# aux_opto_isolation.net
KiCad netlist of a schematic drawn in EAGLE
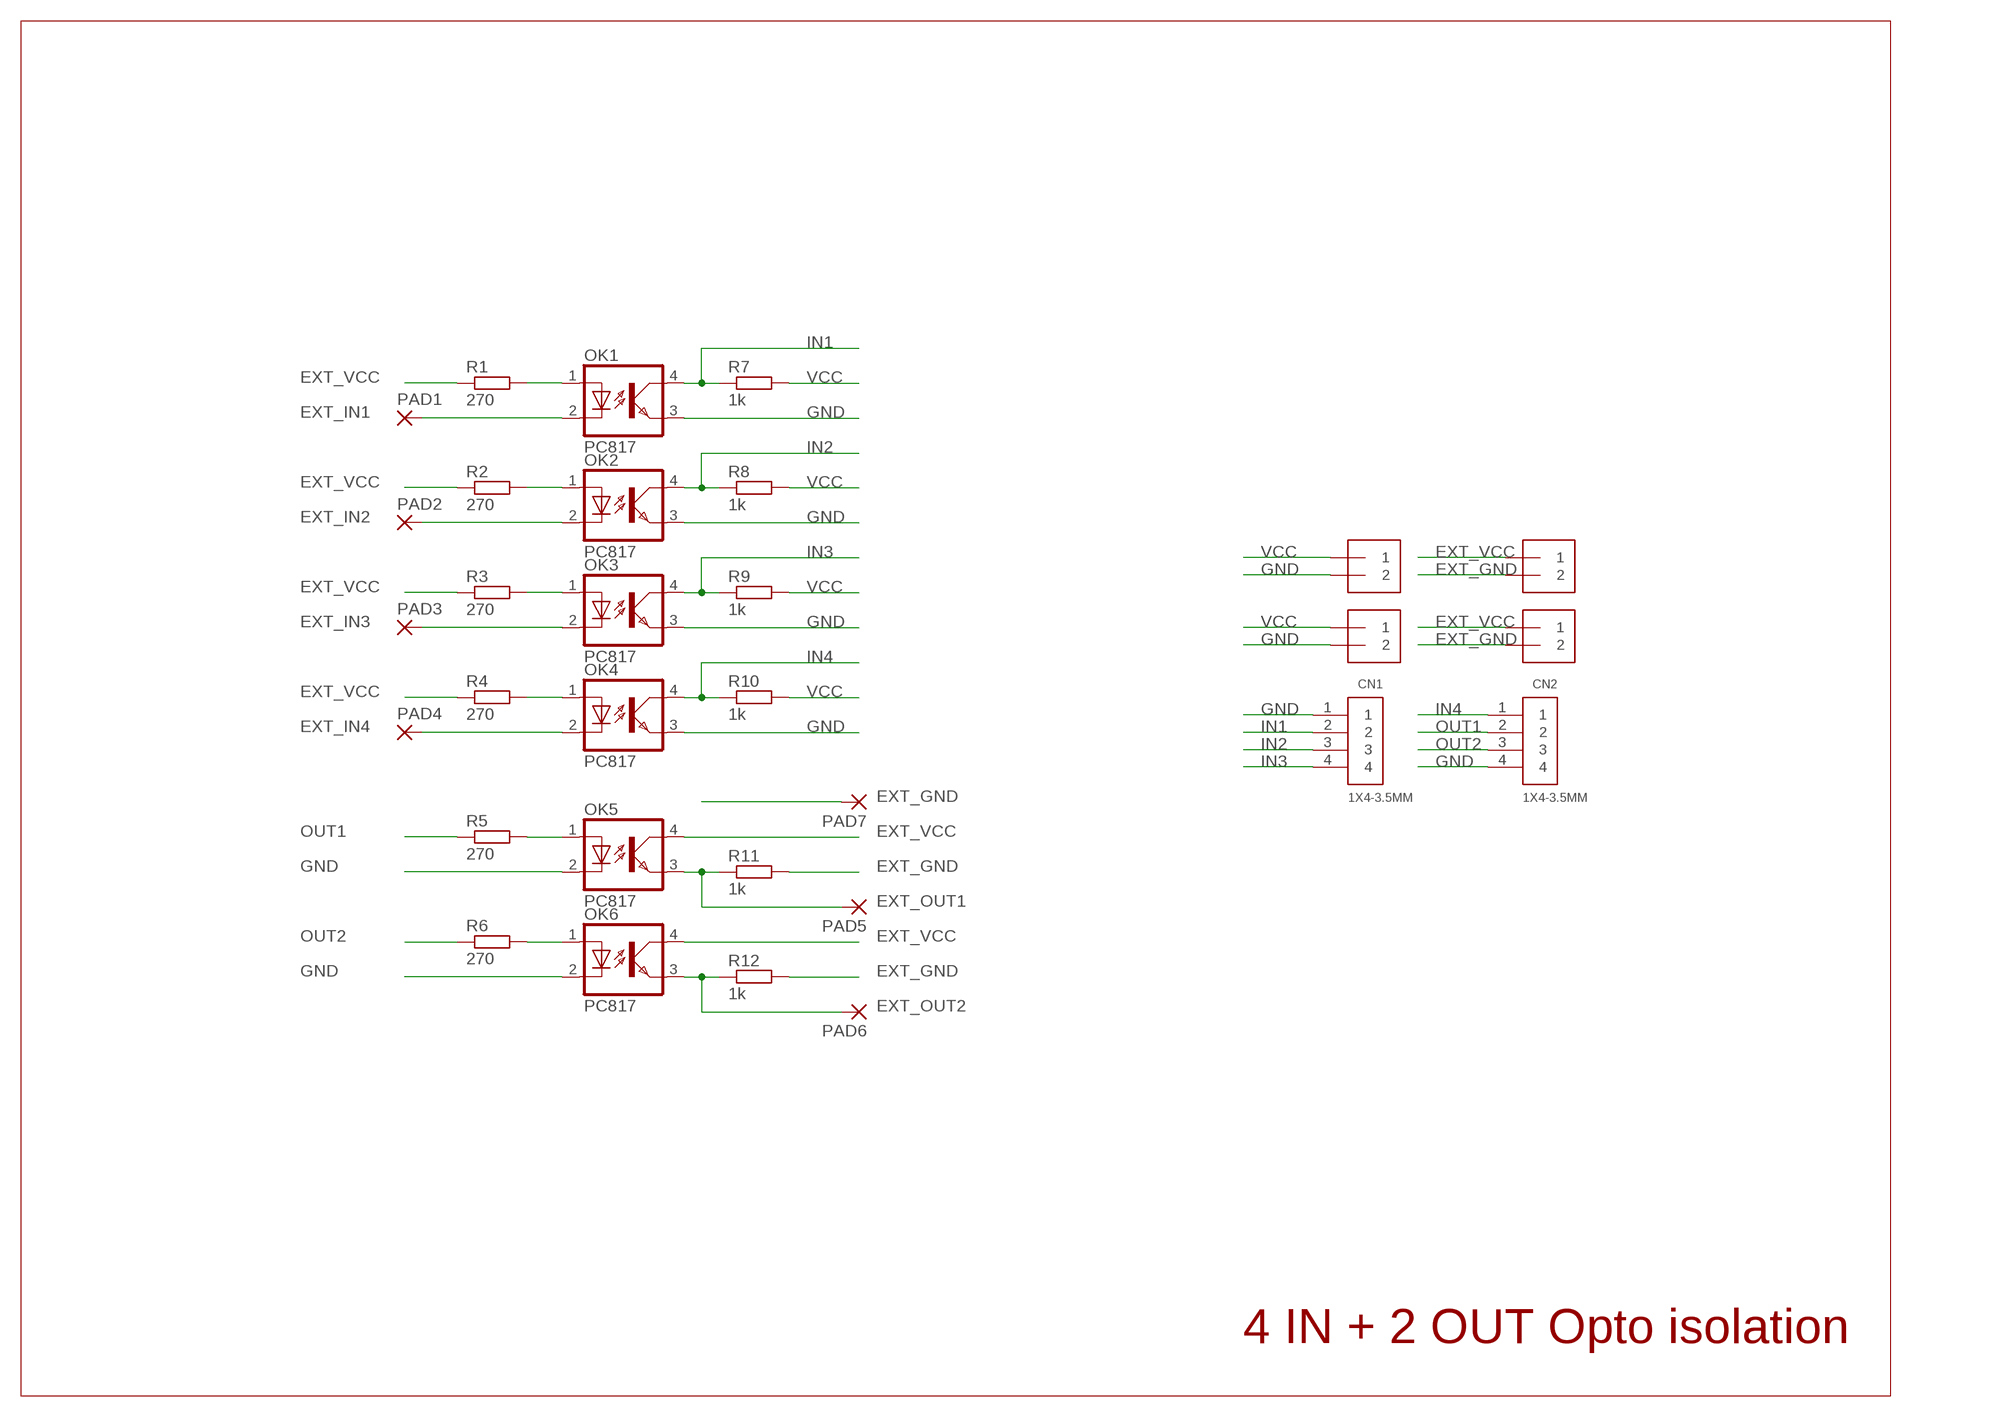
[diagram p0: schematic, sheet 1]

(export (version "E")
  (design (tool "Eeschema 10.0.6"))
  (components
    (comp (ref "CN1")
      (value "1X4-3.5MM")
      (footprint "eagle-import:1X04-3.5MM")
      (libsource (lib "eagle-import") (part "1X4-3.5MM"))
    )
    (comp (ref "CN2")
      (value "1X4-3.5MM")
      (footprint "eagle-import:1X04-3.5MM")
      (libsource (lib "eagle-import") (part "1X4-3.5MM"))
    )
    (comp (ref "J1")
      (value "1X2-3.5MM")
      (footprint "eagle-import:1X2-3.5MM")
      (libsource (lib "eagle-import") (part "1X2-3.5MM"))
    )
    (comp (ref "J2")
      (value "1X2-3.5MM")
      (footprint "eagle-import:1X2-3.5MM")
      (libsource (lib "eagle-import") (part "1X2-3.5MM"))
    )
    (comp (ref "J3")
      (value "1X2-3.5MM")
      (footprint "eagle-import:1X2-3.5MM")
      (libsource (lib "eagle-import") (part "1X2-3.5MM"))
    )
    (comp (ref "J4")
      (value "1X2-3.5MM")
      (footprint "eagle-import:1X2-3.5MM")
      (libsource (lib "eagle-import") (part "1X2-3.5MM"))
    )
    (comp (ref "OK1")
      (value "PC817")
      (footprint "eagle-import:DIL04")
      (fields (field (name "MPN") "PC817X4J000F"))
      (libsource (lib "eagle-import") (part "PC817"))
    )
    (comp (ref "OK2")
      (value "PC817")
      (footprint "eagle-import:DIL04")
      (fields (field (name "MPN") "PC817X4J000F"))
      (libsource (lib "eagle-import") (part "PC817"))
    )
    (comp (ref "OK3")
      (value "PC817")
      (footprint "eagle-import:DIL04")
      (fields (field (name "MPN") "PC817X4J000F"))
      (libsource (lib "eagle-import") (part "PC817"))
    )
    (comp (ref "OK4")
      (value "PC817")
      (footprint "eagle-import:DIL04")
      (fields (field (name "MPN") "PC817X4J000F"))
      (libsource (lib "eagle-import") (part "PC817"))
    )
    (comp (ref "OK5")
      (value "PC817")
      (footprint "eagle-import:DIL04")
      (fields (field (name "MPN") "PC817X4J000F"))
      (libsource (lib "eagle-import") (part "PC817"))
    )
    (comp (ref "OK6")
      (value "PC817")
      (footprint "eagle-import:DIL04")
      (fields (field (name "MPN") "PC817X4J000F"))
      (libsource (lib "eagle-import") (part "PC817"))
    )
    (comp (ref "PAD1")
      (value "2,54/1,0")
      (footprint "eagle-import:2,54_1,0")
      (libsource (lib "eagle-import") (part "2,54/1,0"))
    )
    (comp (ref "PAD2")
      (value "2,54/1,0")
      (footprint "eagle-import:2,54_1,0")
      (libsource (lib "eagle-import") (part "2,54/1,0"))
    )
    (comp (ref "PAD3")
      (value "2,54/1,0")
      (footprint "eagle-import:2,54_1,0")
      (libsource (lib "eagle-import") (part "2,54/1,0"))
    )
    (comp (ref "PAD4")
      (value "2,54/1,0")
      (footprint "eagle-import:2,54_1,0")
      (libsource (lib "eagle-import") (part "2,54/1,0"))
    )
    (comp (ref "PAD5")
      (value "2,54/1,0")
      (footprint "eagle-import:2,54_1,0")
      (libsource (lib "eagle-import") (part "2,54/1,0"))
    )
    (comp (ref "PAD6")
      (value "2,54/1,0")
      (footprint "eagle-import:2,54_1,0")
      (libsource (lib "eagle-import") (part "2,54/1,0"))
    )
    (comp (ref "PAD7")
      (value "2,54/1,0")
      (footprint "eagle-import:2,54_1,0")
      (libsource (lib "eagle-import") (part "2,54/1,0"))
    )
    (comp (ref "R1")
      (value "270")
      (footprint "eagle-import:M0805")
      (libsource (lib "eagle-import") (part "R-EU_M0805"))
    )
    (comp (ref "R2")
      (value "270")
      (footprint "eagle-import:M0805")
      (libsource (lib "eagle-import") (part "R-EU_M0805"))
    )
    (comp (ref "R3")
      (value "270")
      (footprint "eagle-import:M0805")
      (libsource (lib "eagle-import") (part "R-EU_M0805"))
    )
    (comp (ref "R4")
      (value "270")
      (footprint "eagle-import:M0805")
      (libsource (lib "eagle-import") (part "R-EU_M0805"))
    )
    (comp (ref "R5")
      (value "270")
      (footprint "eagle-import:M0805")
      (libsource (lib "eagle-import") (part "R-EU_M0805"))
    )
    (comp (ref "R6")
      (value "270")
      (footprint "eagle-import:M0805")
      (libsource (lib "eagle-import") (part "R-EU_M0805"))
    )
    (comp (ref "R7")
      (value "1k")
      (footprint "eagle-import:M0805")
      (libsource (lib "eagle-import") (part "R-EU_M0805"))
    )
    (comp (ref "R8")
      (value "1k")
      (footprint "eagle-import:M0805")
      (libsource (lib "eagle-import") (part "R-EU_M0805"))
    )
    (comp (ref "R9")
      (value "1k")
      (footprint "eagle-import:M0805")
      (libsource (lib "eagle-import") (part "R-EU_M0805"))
    )
    (comp (ref "R10")
      (value "1k")
      (footprint "eagle-import:M0805")
      (libsource (lib "eagle-import") (part "R-EU_M0805"))
    )
    (comp (ref "R11")
      (value "1k")
      (footprint "eagle-import:M0805")
      (libsource (lib "eagle-import") (part "R-EU_M0805"))
    )
    (comp (ref "R12")
      (value "1k")
      (footprint "eagle-import:M0805")
      (libsource (lib "eagle-import") (part "R-EU_M0805"))
    )
  )
  (nets
    (net (code "1") (name "/EXT_GND") (class "Default")
      (node (ref "J2") (pin "2") (pinfunction "2_2") (pintype "passive"))
      (node (ref "J4") (pin "2") (pinfunction "2_2") (pintype "passive"))
      (node (ref "PAD7") (pin "1") (pinfunction "P_1") (pintype "passive"))
      (node (ref "R11") (pin "2") (pinfunction "2_2") (pintype "passive"))
      (node (ref "R12") (pin "2") (pinfunction "2_2") (pintype "passive"))
    )
    (net (code "2") (name "/EXT_IN1") (class "Default")
      (node (ref "OK1") (pin "2") (pinfunction "C_2") (pintype "passive"))
      (node (ref "PAD1") (pin "1") (pinfunction "P_1") (pintype "passive"))
    )
    (net (code "3") (name "/EXT_IN2") (class "Default")
      (node (ref "OK2") (pin "2") (pinfunction "C_2") (pintype "passive"))
      (node (ref "PAD2") (pin "1") (pinfunction "P_1") (pintype "passive"))
    )
    (net (code "4") (name "/EXT_IN3") (class "Default")
      (node (ref "OK3") (pin "2") (pinfunction "C_2") (pintype "passive"))
      (node (ref "PAD3") (pin "1") (pinfunction "P_1") (pintype "passive"))
    )
    (net (code "5") (name "/EXT_IN4") (class "Default")
      (node (ref "OK4") (pin "2") (pinfunction "C_2") (pintype "passive"))
      (node (ref "PAD4") (pin "1") (pinfunction "P_1") (pintype "passive"))
    )
    (net (code "6") (name "/EXT_OUT1") (class "Default")
      (node (ref "OK5") (pin "3") (pinfunction "EMIT_3") (pintype "passive"))
      (node (ref "PAD5") (pin "1") (pinfunction "P_1") (pintype "passive"))
      (node (ref "R11") (pin "1") (pinfunction "1_1") (pintype "passive"))
    )
    (net (code "7") (name "/EXT_OUT2") (class "Default")
      (node (ref "OK6") (pin "3") (pinfunction "EMIT_3") (pintype "passive"))
      (node (ref "PAD6") (pin "1") (pinfunction "P_1") (pintype "passive"))
      (node (ref "R12") (pin "1") (pinfunction "1_1") (pintype "passive"))
    )
    (net (code "8") (name "/EXT_VCC") (class "Default")
      (node (ref "J2") (pin "1") (pinfunction "1_1") (pintype "passive"))
      (node (ref "J4") (pin "1") (pinfunction "1_1") (pintype "passive"))
      (node (ref "OK5") (pin "4") (pinfunction "COL_4") (pintype "passive"))
      (node (ref "OK6") (pin "4") (pinfunction "COL_4") (pintype "passive"))
      (node (ref "R1") (pin "1") (pinfunction "1_1") (pintype "passive"))
      (node (ref "R2") (pin "1") (pinfunction "1_1") (pintype "passive"))
      (node (ref "R3") (pin "1") (pinfunction "1_1") (pintype "passive"))
      (node (ref "R4") (pin "1") (pinfunction "1_1") (pintype "passive"))
    )
    (net (code "9") (name "/GND") (class "Default")
      (node (ref "CN1") (pin "1") (pinfunction "1_1") (pintype "bidirectional"))
      (node (ref "CN2") (pin "4") (pinfunction "4_4") (pintype "bidirectional"))
      (node (ref "J1") (pin "2") (pinfunction "2_2") (pintype "passive"))
      (node (ref "J3") (pin "2") (pinfunction "2_2") (pintype "passive"))
      (node (ref "OK1") (pin "3") (pinfunction "EMIT_3") (pintype "passive"))
      (node (ref "OK2") (pin "3") (pinfunction "EMIT_3") (pintype "passive"))
      (node (ref "OK3") (pin "3") (pinfunction "EMIT_3") (pintype "passive"))
      (node (ref "OK4") (pin "3") (pinfunction "EMIT_3") (pintype "passive"))
      (node (ref "OK5") (pin "2") (pinfunction "C_2") (pintype "passive"))
      (node (ref "OK6") (pin "2") (pinfunction "C_2") (pintype "passive"))
    )
    (net (code "10") (name "/IN1") (class "Default")
      (node (ref "CN1") (pin "2") (pinfunction "2_2") (pintype "bidirectional"))
      (node (ref "OK1") (pin "4") (pinfunction "COL_4") (pintype "passive"))
      (node (ref "R7") (pin "1") (pinfunction "1_1") (pintype "passive"))
    )
    (net (code "11") (name "/IN2") (class "Default")
      (node (ref "CN1") (pin "3") (pinfunction "3_3") (pintype "bidirectional"))
      (node (ref "OK2") (pin "4") (pinfunction "COL_4") (pintype "passive"))
      (node (ref "R8") (pin "1") (pinfunction "1_1") (pintype "passive"))
    )
    (net (code "12") (name "/IN3") (class "Default")
      (node (ref "CN1") (pin "4") (pinfunction "4_4") (pintype "bidirectional"))
      (node (ref "OK3") (pin "4") (pinfunction "COL_4") (pintype "passive"))
      (node (ref "R9") (pin "1") (pinfunction "1_1") (pintype "passive"))
    )
    (net (code "13") (name "/IN4") (class "Default")
      (node (ref "CN2") (pin "1") (pinfunction "1_1") (pintype "bidirectional"))
      (node (ref "OK4") (pin "4") (pinfunction "COL_4") (pintype "passive"))
      (node (ref "R10") (pin "1") (pinfunction "1_1") (pintype "passive"))
    )
    (net (code "14") (name "/OUT1") (class "Default")
      (node (ref "CN2") (pin "2") (pinfunction "2_2") (pintype "bidirectional"))
      (node (ref "R5") (pin "1") (pinfunction "1_1") (pintype "passive"))
    )
    (net (code "15") (name "/OUT2") (class "Default")
      (node (ref "CN2") (pin "3") (pinfunction "3_3") (pintype "bidirectional"))
      (node (ref "R6") (pin "1") (pinfunction "1_1") (pintype "passive"))
    )
    (net (code "16") (name "/VCC") (class "Default")
      (node (ref "J1") (pin "1") (pinfunction "1_1") (pintype "passive"))
      (node (ref "J3") (pin "1") (pinfunction "1_1") (pintype "passive"))
      (node (ref "R10") (pin "2") (pinfunction "2_2") (pintype "passive"))
      (node (ref "R7") (pin "2") (pinfunction "2_2") (pintype "passive"))
      (node (ref "R8") (pin "2") (pinfunction "2_2") (pintype "passive"))
      (node (ref "R9") (pin "2") (pinfunction "2_2") (pintype "passive"))
    )
    (net (code "17") (name "Net-(OK1-A)") (class "Default")
      (node (ref "OK1") (pin "1") (pinfunction "A_1") (pintype "passive"))
      (node (ref "R1") (pin "2") (pinfunction "2_2") (pintype "passive"))
    )
    (net (code "18") (name "Net-(OK2-A)") (class "Default")
      (node (ref "OK2") (pin "1") (pinfunction "A_1") (pintype "passive"))
      (node (ref "R2") (pin "2") (pinfunction "2_2") (pintype "passive"))
    )
    (net (code "19") (name "Net-(OK3-A)") (class "Default")
      (node (ref "OK3") (pin "1") (pinfunction "A_1") (pintype "passive"))
      (node (ref "R3") (pin "2") (pinfunction "2_2") (pintype "passive"))
    )
    (net (code "20") (name "Net-(OK4-A)") (class "Default")
      (node (ref "OK4") (pin "1") (pinfunction "A_1") (pintype "passive"))
      (node (ref "R4") (pin "2") (pinfunction "2_2") (pintype "passive"))
    )
    (net (code "21") (name "Net-(OK5-A)") (class "Default")
      (node (ref "OK5") (pin "1") (pinfunction "A_1") (pintype "passive"))
      (node (ref "R5") (pin "2") (pinfunction "2_2") (pintype "passive"))
    )
    (net (code "22") (name "Net-(OK6-A)") (class "Default")
      (node (ref "OK6") (pin "1") (pinfunction "A_1") (pintype "passive"))
      (node (ref "R6") (pin "2") (pinfunction "2_2") (pintype "passive"))
    )
  )
)
